# Beam_Freq_to_Volt_Converter.net
KiCad netlist of a schematic drawn in Altium Designer
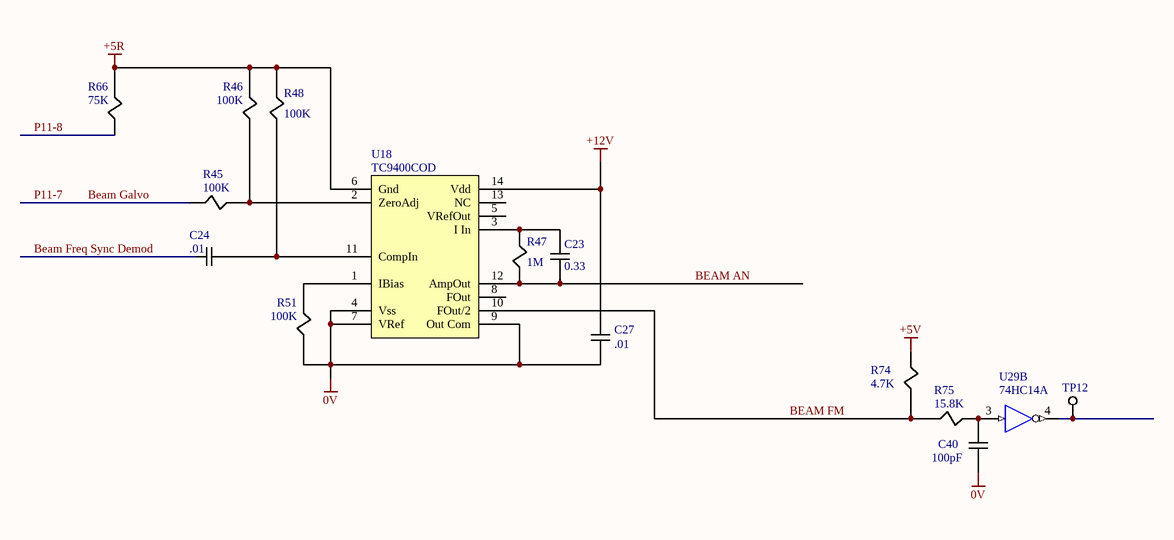
[diagram p0: Beam Freq to Volt Converter.SchDoc]

(export (version "E")
  (design (tool "Eeschema 10.0.6"))
  (components
    (comp (ref "C23") (value "0.33") (footprint "RAD-0.1") (libsource (lib "*") (part "CAP B")))
    (comp (ref "C24") (value ".01") (footprint "RAD-0.1") (libsource (lib "*") (part "CAP B")))
    (comp (ref "C27") (value ".01") (footprint "RAD-0.1") (libsource (lib "*") (part "CAP B")))
    (comp (ref "C40") (value "100pF") (footprint "RAD-0.1") (libsource (lib "*") (part "CAP B")))
    (comp (ref "R45") (value "100K") (footprint "1206") (libsource (lib "*") (part "RES1")))
    (comp (ref "R46") (value "100K") (footprint "1206") (libsource (lib "*") (part "RES1")))
    (comp (ref "R47") (value "1M") (footprint "1206") (libsource (lib "*") (part "RES1")))
    (comp (ref "R48") (value "100K") (footprint "1206") (libsource (lib "*") (part "RES1")))
    (comp (ref "R51") (value "100K") (footprint "1206") (libsource (lib "*") (part "RES1")))
    (comp (ref "R66") (value "75K") (footprint "1206") (libsource (lib "*") (part "RES1")))
    (comp (ref "R74") (value "4.7K") (footprint "1206") (libsource (lib "*") (part "RES1")))
    (comp (ref "R75") (value "15.8K") (footprint "1206") (libsource (lib "*") (part "RES1")))
    (comp (ref "TP12") (value "~") (footprint "TESTPOINT .45") (libsource (lib "*") (part "TESTPOINT A")))
    (comp (ref "U18") (value "TC9400COD") (libsource (lib "*") (part "TC9400 - F/V")))
    (comp (ref "U29") (value "74HC14A") (footprint "DIP14") (libsource (lib "*") (part "7404")))
  )
  (nets
    (net (code "1") (name "+5R") (class "Default")
      (node (ref "R46") (pin "2") (pinfunction "2_2") (pintype "passive"))
      (node (ref "R48") (pin "2") (pinfunction "2_2") (pintype "passive"))
      (node (ref "R66") (pin "2") (pinfunction "2_2") (pintype "passive"))
      (node (ref "U18") (pin "6") (pinfunction "Gnd_6") (pintype "passive"))
    )
    (net (code "2") (name "+5V") (class "Default")
      (node (ref "R74") (pin "2") (pinfunction "2_2") (pintype "passive"))
    )
    (net (code "3") (name "+12V") (class "Default")
      (node (ref "C27") (pin "1") (pinfunction "1_1") (pintype "passive"))
      (node (ref "U18") (pin "14") (pinfunction "Vdd_14") (pintype "passive"))
    )
    (net (code "4") (name "/BEAM AN") (class "Default")
      (node (ref "C23") (pin "1") (pinfunction "1_1") (pintype "passive"))
      (node (ref "R47") (pin "1") (pinfunction "1_1") (pintype "passive"))
      (node (ref "U18") (pin "12") (pinfunction "AmpOut_12") (pintype "passive"))
    )
    (net (code "5") (name "/BEAM FM") (class "Default")
      (node (ref "R74") (pin "1") (pinfunction "1_1") (pintype "passive"))
      (node (ref "R75") (pin "1") (pinfunction "1_1") (pintype "passive"))
      (node (ref "U18") (pin "10") (pinfunction "FOut/2_10") (pintype "passive"))
    )
    (net (code "6") (name "/Beam Freq Sync Demod") (class "Default")
      (node (ref "C24") (pin "1") (pinfunction "1_1") (pintype "passive"))
    )
    (net (code "7") (name "/Beam Galvo") (class "Default")
      (node (ref "R45") (pin "1") (pinfunction "1_1") (pintype "passive"))
    )
    (net (code "8") (name "/P11-8") (class "Default")
      (node (ref "R66") (pin "1") (pinfunction "1_1") (pintype "passive"))
    )
    (net (code "9") (name "0V") (class "Default")
      (node (ref "C27") (pin "2") (pinfunction "2_2") (pintype "passive"))
      (node (ref "C40") (pin "2") (pinfunction "2_2") (pintype "passive"))
      (node (ref "R51") (pin "1") (pinfunction "1_1") (pintype "passive"))
      (node (ref "U18") (pin "4") (pinfunction "Vss_4") (pintype "passive"))
      (node (ref "U18") (pin "7") (pinfunction "VRef_7") (pintype "passive"))
      (node (ref "U18") (pin "9") (pinfunction "Out_Com_9") (pintype "passive"))
    )
    (net (code "10") (name "GND") (class "Default")
      (node (ref "U29") (pin "7") (pinfunction "GND_7") (pintype "power_in"))
    )
    (net (code "11") (name "Net-(U18-CompIn)") (class "Default")
      (node (ref "C24") (pin "2") (pinfunction "2_2") (pintype "passive"))
      (node (ref "R48") (pin "1") (pinfunction "1_1") (pintype "passive"))
      (node (ref "U18") (pin "11") (pinfunction "CompIn_11") (pintype "passive"))
    )
    (net (code "12") (name "Net-(U18-IBias)") (class "Default")
      (node (ref "R51") (pin "2") (pinfunction "2_2") (pintype "passive"))
      (node (ref "U18") (pin "1") (pinfunction "IBias_1") (pintype "passive"))
    )
    (net (code "13") (name "Net-(U18-I_In)") (class "Default")
      (node (ref "C23") (pin "2") (pinfunction "2_2") (pintype "passive"))
      (node (ref "R47") (pin "2") (pinfunction "2_2") (pintype "passive"))
      (node (ref "U18") (pin "3") (pinfunction "I_In_3") (pintype "passive"))
    )
    (net (code "14") (name "Net-(U18-ZeroAdj)") (class "Default")
      (node (ref "R45") (pin "2") (pinfunction "2_2") (pintype "passive"))
      (node (ref "R46") (pin "1") (pinfunction "1_1") (pintype "passive"))
      (node (ref "U18") (pin "2") (pinfunction "ZeroAdj_2") (pintype "passive"))
    )
    (net (code "15") (name "Net-(U29B-A)") (class "Default")
      (node (ref "C40") (pin "1") (pinfunction "1_1") (pintype "passive"))
      (node (ref "R75") (pin "2") (pinfunction "2_2") (pintype "passive"))
      (node (ref "U29") (pin "3") (pinfunction "A_3") (pintype "input"))
    )
    (net (code "16") (name "Net-(U29B-Y)") (class "Default")
      (node (ref "TP12") (pin "1") (pinfunction "1_1") (pintype "passive"))
      (node (ref "U29") (pin "4") (pinfunction "Y_4") (pintype "output"))
    )
    (net (code "17") (name "VCC") (class "Default")
      (node (ref "U29") (pin "14") (pinfunction "VCC_14") (pintype "power_in"))
    )
    (net (code "18") (name "unconnected-(U18-FOut-Pad8)") (class "Default")
      (node (ref "U18") (pin "8") (pinfunction "FOut_8") (pintype "passive"))
    )
    (net (code "19") (name "unconnected-(U18-NC-Pad13)") (class "Default")
      (node (ref "U18") (pin "13") (pinfunction "NC_13") (pintype "passive"))
    )
    (net (code "20") (name "unconnected-(U18-VRefOut-Pad5)") (class "Default")
      (node (ref "U18") (pin "5") (pinfunction "VRefOut_5") (pintype "passive"))
    )
  )
)
